# esp_ble.net
KiCad netlist of a schematic drawn in EAGLE
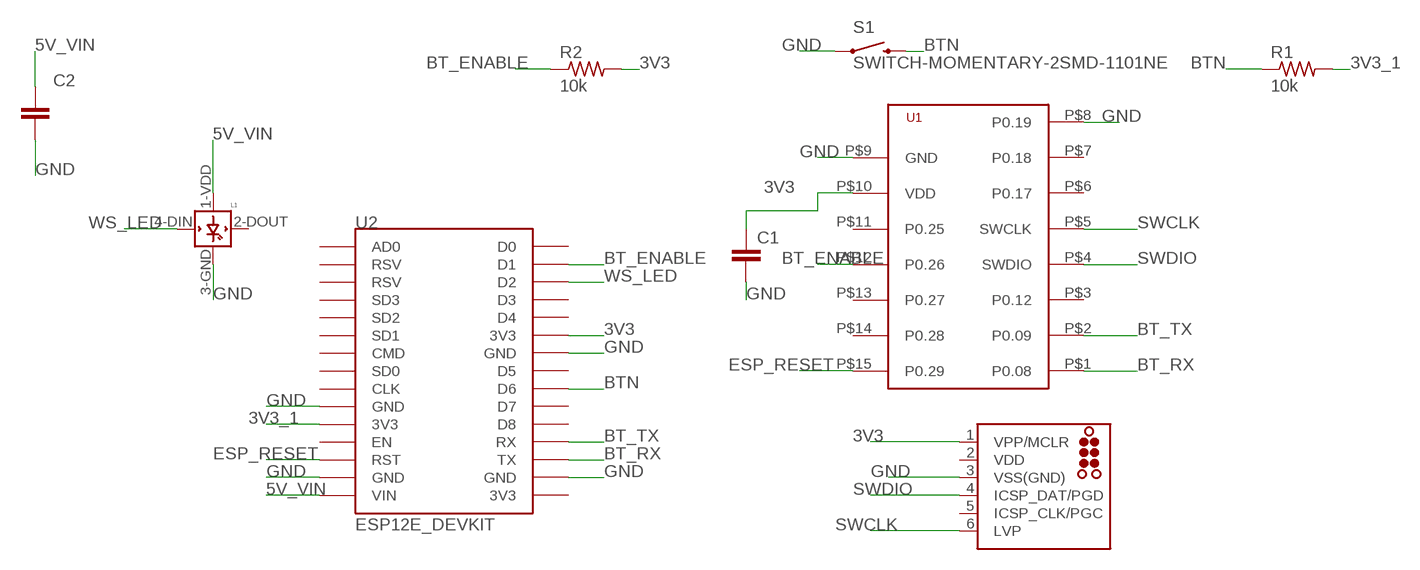
[diagram p0: schematic, sheet 1]

(export (version "E")
  (design (tool "Eeschema 10.0.6"))
  (components
    (comp (ref "C1")
      (value "CAP0603-CAP")
      (footprint "eagle-import:0603-CAP")
      (libsource (lib "eagle-import") (part "CAP0603-CAP"))
    )
    (comp (ref "C2")
      (value "CAPACITOR_NPOL-0603")
      (footprint "eagle-import:C603")
      (libsource (lib "eagle-import") (part "CAPACITOR_NPOL-0603"))
    )
    (comp (ref "J1")
      (value "TC2030-MCP-NL")
      (footprint "eagle-import:TC2030-MCP-NL")
      (libsource (lib "eagle-import") (part "TC2030-MCP-NL"))
    )
    (comp (ref "L1")
      (value "WS2812B")
      (footprint "eagle-import:WS2812B")
      (libsource (lib "eagle-import") (part "WS2812B"))
    )
    (comp (ref "R1")
      (value "10k")
      (footprint "eagle-import:R0603")
      (libsource (lib "eagle-import") (part "RESISTOR0603"))
    )
    (comp (ref "R2")
      (value "10k")
      (footprint "eagle-import:R0603")
      (libsource (lib "eagle-import") (part "RESISTOR0603"))
    )
    (comp (ref "S1")
      (value "SWITCH-MOMENTARY-2SMD-1101NE")
      (footprint "eagle-import:TACTILE-SWITCH-1101NE")
      (libsource (lib "eagle-import") (part "SWITCH-MOMENTARY-2SMD-1101NE"))
    )
    (comp (ref "U1")
      (value "PTR5518")
      (footprint "eagle-import:PTR5518")
      (libsource (lib "eagle-import") (part "PTR5518"))
    )
    (comp (ref "U2")
      (value "ESP12E_DEVKIT")
      (footprint "eagle-import:ESP12E_DEVKIT")
      (libsource (lib "eagle-import") (part "ESP12E_DEVKIT"))
    )
  )
  (nets
    (net (code "1") (name "/3V3") (class "Default")
      (node (ref "C1") (pin "1") (pinfunction "1_1") (pintype "passive"))
      (node (ref "J1") (pin "1") (pinfunction "VPP/MCLR_1") (pintype "passive"))
      (node (ref "R2") (pin "2") (pinfunction "2_2") (pintype "passive"))
      (node (ref "U1") (pin "P$10") (pinfunction "VDD_P$10") (pintype "power_in"))
      (node (ref "U2") (pin "3V3@1") (pinfunction "3V3_3V3@1") (pintype "bidirectional"))
    )
    (net (code "2") (name "/3V3_1") (class "Default")
      (node (ref "R1") (pin "2") (pinfunction "2_2") (pintype "passive"))
      (node (ref "U2") (pin "3V3@0") (pinfunction "3V3_3V3@0") (pintype "bidirectional"))
    )
    (net (code "3") (name "/5V_VIN") (class "Default")
      (node (ref "C2") (pin "1") (pinfunction "1_1") (pintype "passive"))
      (node (ref "L1") (pin "1-VDD") (pinfunction "VDD_1-VDD") (pintype "bidirectional"))
      (node (ref "U2") (pin "VIN") (pinfunction "VIN_VIN") (pintype "bidirectional"))
    )
    (net (code "4") (name "/BTN") (class "Default")
      (node (ref "R1") (pin "1") (pinfunction "1_1") (pintype "passive"))
      (node (ref "S1") (pin "2") (pinfunction "2_2") (pintype "passive"))
      (node (ref "U2") (pin "D6") (pinfunction "D6_D6") (pintype "bidirectional"))
    )
    (net (code "5") (name "/BT_ENABLE") (class "Default")
      (node (ref "R2") (pin "1") (pinfunction "1_1") (pintype "passive"))
      (node (ref "U1") (pin "P$12") (pinfunction "P0.26_P$12") (pintype "bidirectional"))
      (node (ref "U2") (pin "D1") (pinfunction "D1_D1") (pintype "bidirectional"))
    )
    (net (code "6") (name "/BT_RX") (class "Default")
      (node (ref "U1") (pin "P$1") (pinfunction "P0.08_P$1") (pintype "bidirectional"))
      (node (ref "U2") (pin "TX") (pinfunction "TX_TX") (pintype "bidirectional"))
    )
    (net (code "7") (name "/BT_TX") (class "Default")
      (node (ref "U1") (pin "P$2") (pinfunction "P0.09_P$2") (pintype "bidirectional"))
      (node (ref "U2") (pin "RX") (pinfunction "RX_RX") (pintype "bidirectional"))
    )
    (net (code "8") (name "/ESP_RESET") (class "Default")
      (node (ref "U1") (pin "P$15") (pinfunction "P0.29_P$15") (pintype "bidirectional"))
      (node (ref "U2") (pin "RST") (pinfunction "RST_RST") (pintype "bidirectional"))
    )
    (net (code "9") (name "/GND") (class "Default")
      (node (ref "C1") (pin "2") (pinfunction "2_2") (pintype "passive"))
      (node (ref "C2") (pin "2") (pinfunction "2_2") (pintype "passive"))
      (node (ref "J1") (pin "3") (pinfunction "VSS(GND)_3") (pintype "power_in"))
      (node (ref "L1") (pin "3-GND") (pinfunction "GND_3-GND") (pintype "bidirectional"))
      (node (ref "S1") (pin "1") (pinfunction "1_1") (pintype "passive"))
      (node (ref "U1") (pin "P$8") (pinfunction "P0.19_P$8") (pintype "bidirectional"))
      (node (ref "U1") (pin "P$9") (pinfunction "GND_P$9") (pintype "power_in"))
      (node (ref "U2") (pin "GND@0") (pinfunction "GND_GND@0") (pintype "bidirectional"))
      (node (ref "U2") (pin "GND@1") (pinfunction "GND_GND@1") (pintype "bidirectional"))
      (node (ref "U2") (pin "GND@2") (pinfunction "GND_GND@2") (pintype "bidirectional"))
      (node (ref "U2") (pin "GND@3") (pinfunction "GND_GND@3") (pintype "bidirectional"))
    )
    (net (code "10") (name "/SWCLK") (class "Default")
      (node (ref "J1") (pin "6") (pinfunction "LVP_6") (pintype "bidirectional"))
      (node (ref "U1") (pin "P$5") (pinfunction "SWCLK_P$5") (pintype "bidirectional"))
    )
    (net (code "11") (name "/SWDIO") (class "Default")
      (node (ref "J1") (pin "4") (pinfunction "ICSP_DAT/PGD_4") (pintype "bidirectional"))
      (node (ref "U1") (pin "P$4") (pinfunction "SWDIO_P$4") (pintype "bidirectional"))
    )
    (net (code "12") (name "/VDD") (class "Default")
      (node (ref "J1") (pin "2") (pinfunction "VDD_2") (pintype "power_in"))
    )
    (net (code "13") (name "/WS_LED") (class "Default")
      (node (ref "L1") (pin "4-DIN") (pinfunction "DIN_4-DIN") (pintype "input"))
      (node (ref "U2") (pin "D2") (pinfunction "D2_D2") (pintype "bidirectional"))
    )
    (net (code "14") (name "unconnected-(J1-ICSP_CLK{slash}PGC-Pad5)") (class "Default")
      (node (ref "J1") (pin "5") (pinfunction "ICSP_CLK/PGC_5") (pintype "output"))
    )
    (net (code "15") (name "unconnected-(L1-DOUT-Pad2-DOUT)") (class "Default")
      (node (ref "L1") (pin "2-DOUT") (pinfunction "DOUT_2-DOUT") (pintype "output"))
    )
    (net (code "16") (name "unconnected-(U1-P0.12-PadP$3)") (class "Default")
      (node (ref "U1") (pin "P$3") (pinfunction "P0.12_P$3") (pintype "bidirectional"))
    )
    (net (code "17") (name "unconnected-(U1-P0.17-PadP$6)") (class "Default")
      (node (ref "U1") (pin "P$6") (pinfunction "P0.17_P$6") (pintype "bidirectional"))
    )
    (net (code "18") (name "unconnected-(U1-P0.18-PadP$7)") (class "Default")
      (node (ref "U1") (pin "P$7") (pinfunction "P0.18_P$7") (pintype "bidirectional"))
    )
    (net (code "19") (name "unconnected-(U1-P0.25-PadP$11)") (class "Default")
      (node (ref "U1") (pin "P$11") (pinfunction "P0.25_P$11") (pintype "bidirectional"))
    )
    (net (code "20") (name "unconnected-(U1-P0.27-PadP$13)") (class "Default")
      (node (ref "U1") (pin "P$13") (pinfunction "P0.27_P$13") (pintype "bidirectional"))
    )
    (net (code "21") (name "unconnected-(U1-P0.28-PadP$14)") (class "Default")
      (node (ref "U1") (pin "P$14") (pinfunction "P0.28_P$14") (pintype "bidirectional"))
    )
    (net (code "22") (name "unconnected-(U2-3V3-Pad3V3@2)") (class "Default")
      (node (ref "U2") (pin "3V3@2") (pinfunction "3V3_3V3@2") (pintype "bidirectional"))
    )
    (net (code "23") (name "unconnected-(U2-PadAD0)") (class "Default")
      (node (ref "U2") (pin "AD0") (pinfunction "AD0_AD0") (pintype "bidirectional"))
    )
    (net (code "24") (name "unconnected-(U2-PadCLK)") (class "Default")
      (node (ref "U2") (pin "CLK") (pinfunction "CLK_CLK") (pintype "bidirectional"))
    )
    (net (code "25") (name "unconnected-(U2-PadCMD)") (class "Default")
      (node (ref "U2") (pin "CMD") (pinfunction "CMD_CMD") (pintype "bidirectional"))
    )
    (net (code "26") (name "unconnected-(U2-PadD0)") (class "Default")
      (node (ref "U2") (pin "D0") (pinfunction "D0_D0") (pintype "bidirectional"))
    )
    (net (code "27") (name "unconnected-(U2-PadD3)") (class "Default")
      (node (ref "U2") (pin "D3") (pinfunction "D3_D3") (pintype "bidirectional"))
    )
    (net (code "28") (name "unconnected-(U2-PadD4)") (class "Default")
      (node (ref "U2") (pin "D4") (pinfunction "D4_D4") (pintype "bidirectional"))
    )
    (net (code "29") (name "unconnected-(U2-PadD5)") (class "Default")
      (node (ref "U2") (pin "D5") (pinfunction "D5_D5") (pintype "bidirectional"))
    )
    (net (code "30") (name "unconnected-(U2-PadD7)") (class "Default")
      (node (ref "U2") (pin "D7") (pinfunction "D7_D7") (pintype "bidirectional"))
    )
    (net (code "31") (name "unconnected-(U2-PadD8)") (class "Default")
      (node (ref "U2") (pin "D8") (pinfunction "D8_D8") (pintype "bidirectional"))
    )
    (net (code "32") (name "unconnected-(U2-PadEN)") (class "Default")
      (node (ref "U2") (pin "EN") (pinfunction "EN_EN") (pintype "bidirectional"))
    )
    (net (code "33") (name "unconnected-(U2-PadSD0)") (class "Default")
      (node (ref "U2") (pin "SD0") (pinfunction "SD0_SD0") (pintype "bidirectional"))
    )
    (net (code "34") (name "unconnected-(U2-PadSD1)") (class "Default")
      (node (ref "U2") (pin "SD1") (pinfunction "SD1_SD1") (pintype "bidirectional"))
    )
    (net (code "35") (name "unconnected-(U2-PadSD2)") (class "Default")
      (node (ref "U2") (pin "SD2") (pinfunction "SD2_SD2") (pintype "bidirectional"))
    )
    (net (code "36") (name "unconnected-(U2-PadSD3)") (class "Default")
      (node (ref "U2") (pin "SD3") (pinfunction "SD3_SD3") (pintype "bidirectional"))
    )
    (net (code "37") (name "unconnected-(U2-RSV-PadRSV@0)") (class "Default")
      (node (ref "U2") (pin "RSV@0") (pinfunction "RSV_RSV@0") (pintype "bidirectional"))
    )
    (net (code "38") (name "unconnected-(U2-RSV-PadRSV@1)") (class "Default")
      (node (ref "U2") (pin "RSV@1") (pinfunction "RSV_RSV@1") (pintype "bidirectional"))
    )
  )
)
